# cytron.net
KiCad netlist of a schematic drawn in EAGLE
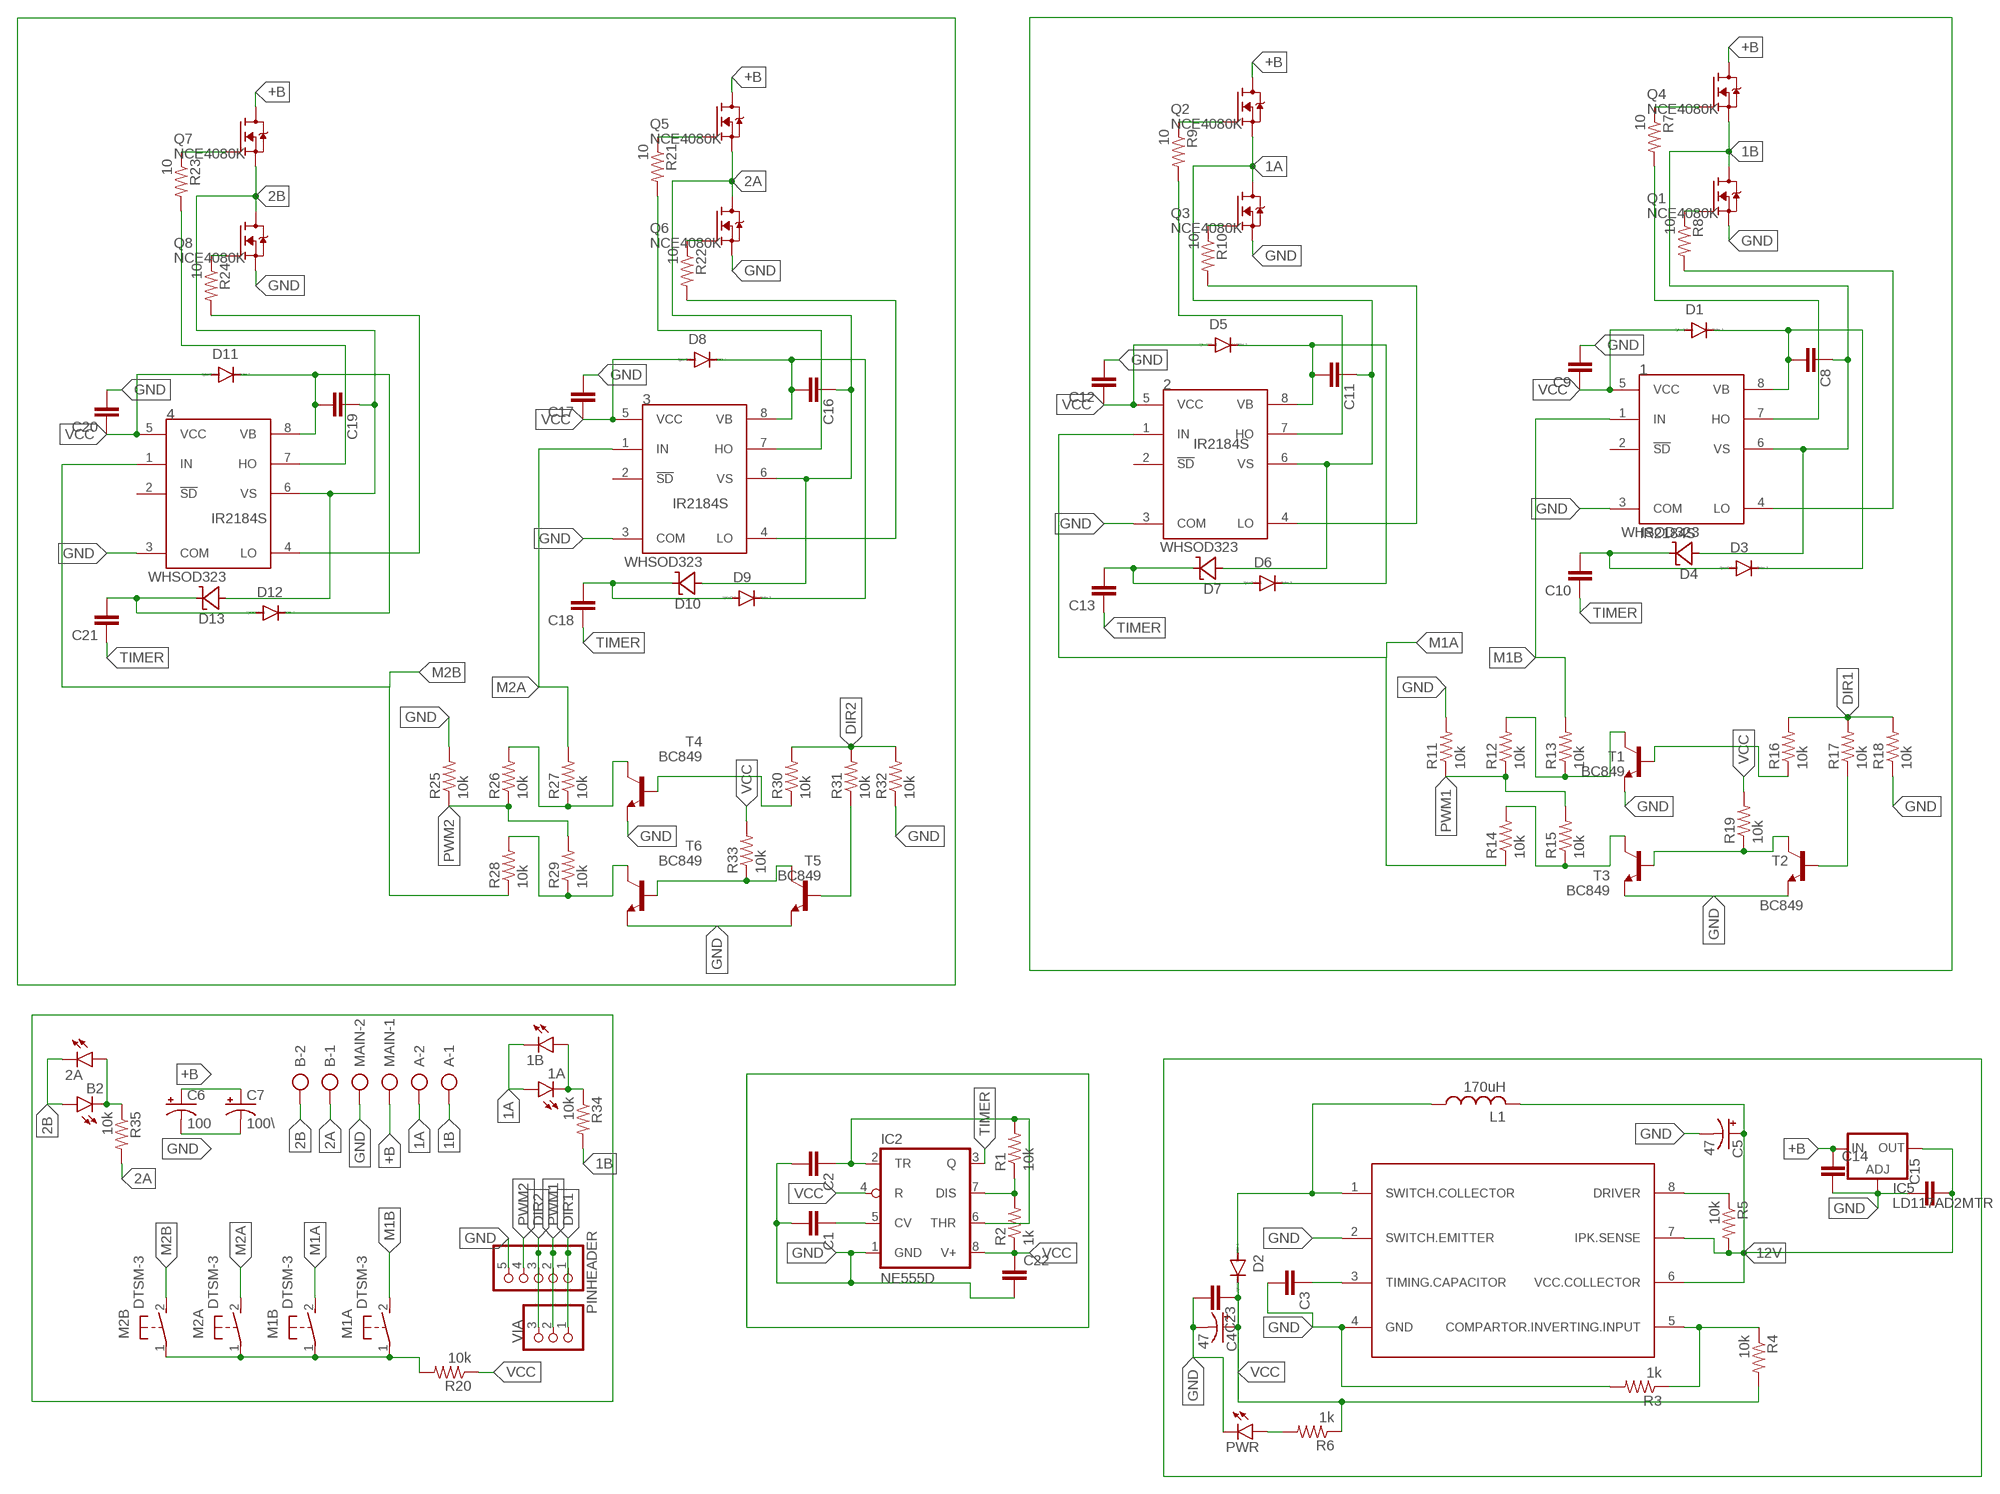
[diagram p0: schematic, sheet 1]

(export (version "E")
  (design (tool "Eeschema 10.0.6"))
  (components
    (comp (ref "1")
      (value "IR2184S")
      (footprint "eagle-import:SO08")
      (libsource (lib "eagle-import") (part "IR2184S"))
    )
    (comp (ref "1A")
      (value "LEDCHIPLED_1206")
      (footprint "eagle-import:CHIPLED_1206")
      (libsource (lib "eagle-import") (part "LEDCHIPLED_1206"))
    )
    (comp (ref "1B")
      (value "LEDCHIPLED_1206")
      (footprint "eagle-import:CHIPLED_1206")
      (libsource (lib "eagle-import") (part "LEDCHIPLED_1206"))
    )
    (comp (ref "2")
      (value "IR2184S")
      (footprint "eagle-import:SO08")
      (libsource (lib "eagle-import") (part "IR2184S"))
    )
    (comp (ref "2A")
      (value "LEDCHIPLED_1206")
      (footprint "eagle-import:CHIPLED_1206")
      (libsource (lib "eagle-import") (part "LEDCHIPLED_1206"))
    )
    (comp (ref "3")
      (value "IR2184S")
      (footprint "eagle-import:SO08")
      (libsource (lib "eagle-import") (part "IR2184S"))
    )
    (comp (ref "4")
      (value "IR2184S")
      (footprint "eagle-import:SO08")
      (libsource (lib "eagle-import") (part "IR2184S"))
    )
    (comp (ref "A")
      (value "AK300/22")
      (footprint "eagle-import:XTALRR488W60L1090T465H350B")
      (libsource (lib "eagle-import") (part "AK300/22"))
    )
    (comp (ref "B")
      (value "AK300/22")
      (footprint "eagle-import:XTALRR488W60L1090T465H350B")
      (libsource (lib "eagle-import") (part "AK300/22"))
    )
    (comp (ref "B2")
      (value "LEDCHIPLED_1206")
      (footprint "eagle-import:CHIPLED_1206")
      (libsource (lib "eagle-import") (part "LEDCHIPLED_1206"))
    )
    (comp (ref "C1")
      (value "C-EUC0805K")
      (footprint "eagle-import:C0805K")
      (libsource (lib "eagle-import") (part "C-EUC0805K"))
    )
    (comp (ref "C2")
      (value "C-EUC0805K")
      (footprint "eagle-import:C0805K")
      (libsource (lib "eagle-import") (part "C-EUC0805K"))
    )
    (comp (ref "C3")
      (value "C-EUC0805K")
      (footprint "eagle-import:C0805K")
      (libsource (lib "eagle-import") (part "C-EUC0805K"))
    )
    (comp (ref "C4")
      (value "47")
      (footprint "eagle-import:140CLH-1014")
      (libsource (lib "eagle-import") (part "CPOL-US140CLH-1014"))
    )
    (comp (ref "C5")
      (value "47")
      (footprint "eagle-import:140CLH-1014")
      (libsource (lib "eagle-import") (part "CPOL-US140CLH-1014"))
    )
    (comp (ref "C6")
      (value "100")
      (footprint "eagle-import:SANYO-OSCON_SMD_F12")
      (libsource (lib "eagle-import") (part "CPOL-USSANYO_SMD_F12"))
    )
    (comp (ref "C7")
      (value "100\\")
      (footprint "eagle-import:SANYO-OSCON_SMD_F12")
      (libsource (lib "eagle-import") (part "CPOL-USSANYO_SMD_F12"))
    )
    (comp (ref "C8")
      (value "C-EUC0805K")
      (footprint "eagle-import:C0805K")
      (libsource (lib "eagle-import") (part "C-EUC0805K"))
    )
    (comp (ref "C9")
      (value "C-EUC0805K")
      (footprint "eagle-import:C0805K")
      (libsource (lib "eagle-import") (part "C-EUC0805K"))
    )
    (comp (ref "C10")
      (value "C-EUC0805K")
      (footprint "eagle-import:C0805K")
      (libsource (lib "eagle-import") (part "C-EUC0805K"))
    )
    (comp (ref "C11")
      (value "C-EUC0805K")
      (footprint "eagle-import:C0805K")
      (libsource (lib "eagle-import") (part "C-EUC0805K"))
    )
    (comp (ref "C12")
      (value "C-EUC0805K")
      (footprint "eagle-import:C0805K")
      (libsource (lib "eagle-import") (part "C-EUC0805K"))
    )
    (comp (ref "C13")
      (value "C-EUC0805K")
      (footprint "eagle-import:C0805K")
      (libsource (lib "eagle-import") (part "C-EUC0805K"))
    )
    (comp (ref "C14")
      (value "C-EUC0805K")
      (footprint "eagle-import:C0805K")
      (libsource (lib "eagle-import") (part "C-EUC0805K"))
    )
    (comp (ref "C15")
      (value "C-EUC0805K")
      (footprint "eagle-import:C0805K")
      (libsource (lib "eagle-import") (part "C-EUC0805K"))
    )
    (comp (ref "C16")
      (value "C-EUC0805K")
      (footprint "eagle-import:C0805K")
      (libsource (lib "eagle-import") (part "C-EUC0805K"))
    )
    (comp (ref "C17")
      (value "C-EUC0805K")
      (footprint "eagle-import:C0805K")
      (libsource (lib "eagle-import") (part "C-EUC0805K"))
    )
    (comp (ref "C18")
      (value "C-EUC0805K")
      (footprint "eagle-import:C0805K")
      (libsource (lib "eagle-import") (part "C-EUC0805K"))
    )
    (comp (ref "C19")
      (value "C-EUC0805K")
      (footprint "eagle-import:C0805K")
      (libsource (lib "eagle-import") (part "C-EUC0805K"))
    )
    (comp (ref "C20")
      (value "C-EUC0805K")
      (footprint "eagle-import:C0805K")
      (libsource (lib "eagle-import") (part "C-EUC0805K"))
    )
    (comp (ref "C21")
      (value "C-EUC0805K")
      (footprint "eagle-import:C0805K")
      (libsource (lib "eagle-import") (part "C-EUC0805K"))
    )
    (comp (ref "C22")
      (value "C-EUC0805K")
      (footprint "eagle-import:C0805K")
      (libsource (lib "eagle-import") (part "C-EUC0805K"))
    )
    (comp (ref "C23")
      (value "C-EUC0805K")
      (footprint "eagle-import:C0805K")
      (libsource (lib "eagle-import") (part "C-EUC0805K"))
    )
    (comp (ref "D1")
      (value "DIODE-SMB")
      (footprint "eagle-import:SMB")
      (libsource (lib "eagle-import") (part "DIODE-SMB"))
    )
    (comp (ref "D2")
      (value "DIODE-SMB")
      (footprint "eagle-import:SMB")
      (libsource (lib "eagle-import") (part "DIODE-SMB"))
    )
    (comp (ref "D3")
      (value "DIODE-SMB")
      (footprint "eagle-import:SMB")
      (libsource (lib "eagle-import") (part "DIODE-SMB"))
    )
    (comp (ref "D4")
      (value "WHSOD323")
      (footprint "eagle-import:SOD323-W")
      (libsource (lib "eagle-import") (part "WHSOD323"))
    )
    (comp (ref "D5")
      (value "DIODE-SMB")
      (footprint "eagle-import:SMB")
      (libsource (lib "eagle-import") (part "DIODE-SMB"))
    )
    (comp (ref "D6")
      (value "DIODE-SMB")
      (footprint "eagle-import:SMB")
      (libsource (lib "eagle-import") (part "DIODE-SMB"))
    )
    (comp (ref "D7")
      (value "WHSOD323")
      (footprint "eagle-import:SOD323-W")
      (libsource (lib "eagle-import") (part "WHSOD323"))
    )
    (comp (ref "D8")
      (value "DIODE-SMB")
      (footprint "eagle-import:SMB")
      (libsource (lib "eagle-import") (part "DIODE-SMB"))
    )
    (comp (ref "D9")
      (value "DIODE-SMB")
      (footprint "eagle-import:SMB")
      (libsource (lib "eagle-import") (part "DIODE-SMB"))
    )
    (comp (ref "D10")
      (value "WHSOD323")
      (footprint "eagle-import:SOD323-W")
      (libsource (lib "eagle-import") (part "WHSOD323"))
    )
    (comp (ref "D11")
      (value "DIODE-SMB")
      (footprint "eagle-import:SMB")
      (libsource (lib "eagle-import") (part "DIODE-SMB"))
    )
    (comp (ref "D12")
      (value "DIODE-SMB")
      (footprint "eagle-import:SMB")
      (libsource (lib "eagle-import") (part "DIODE-SMB"))
    )
    (comp (ref "D13")
      (value "WHSOD323")
      (footprint "eagle-import:SOD323-W")
      (libsource (lib "eagle-import") (part "WHSOD323"))
    )
    (comp (ref "IC2")
      (value "NE555D")
      (footprint "eagle-import:SO08")
      (libsource (lib "eagle-import") (part "555DNE"))
    )
    (comp (ref "IC5")
      (value "LD117AD2MTR")
      (footprint "eagle-import:D2PACK")
      (libsource (lib "eagle-import") (part "LD117A?D2MTR"))
    )
    (comp (ref "L1")
      (value "170uH")
      (footprint "eagle-import:POWER-CHOKE_WE-TPC")
      (libsource (lib "eagle-import") (part "L-USWE-TPC"))
    )
    (comp (ref "M1A")
      (value "DTSM-3")
      (footprint "eagle-import:DTSM-3")
      (libsource (lib "eagle-import") (part "DTSM-3"))
    )
    (comp (ref "M1B")
      (value "DTSM-3")
      (footprint "eagle-import:DTSM-3")
      (libsource (lib "eagle-import") (part "DTSM-3"))
    )
    (comp (ref "M2A")
      (value "DTSM-3")
      (footprint "eagle-import:DTSM-3")
      (libsource (lib "eagle-import") (part "DTSM-3"))
    )
    (comp (ref "M2B")
      (value "DTSM-3")
      (footprint "eagle-import:DTSM-3")
      (libsource (lib "eagle-import") (part "DTSM-3"))
    )
    (comp (ref "MAIN")
      (value "AK300/22")
      (footprint "eagle-import:XTALRR488W60L1090T465H350B")
      (libsource (lib "eagle-import") (part "AK300/22"))
    )
    (comp (ref "PINHEADER")
      (value "PINHD-1X5")
      (footprint "eagle-import:1X05")
      (libsource (lib "eagle-import") (part "PINHD-1X5"))
    )
    (comp (ref "PWR")
      (value "LEDCHIPLED_1206")
      (footprint "eagle-import:CHIPLED_1206")
      (libsource (lib "eagle-import") (part "LEDCHIPLED_1206"))
    )
    (comp (ref "Q1")
      (value "NCE4080K")
      (footprint "eagle-import:TO252")
      (libsource (lib "eagle-import") (part "NCE4080K"))
    )
    (comp (ref "Q2")
      (value "NCE4080K")
      (footprint "eagle-import:TO252")
      (libsource (lib "eagle-import") (part "NCE4080K"))
    )
    (comp (ref "Q3")
      (value "NCE4080K")
      (footprint "eagle-import:TO252")
      (libsource (lib "eagle-import") (part "NCE4080K"))
    )
    (comp (ref "Q4")
      (value "NCE4080K")
      (footprint "eagle-import:TO252")
      (libsource (lib "eagle-import") (part "NCE4080K"))
    )
    (comp (ref "Q5")
      (value "NCE4080K")
      (footprint "eagle-import:TO252")
      (libsource (lib "eagle-import") (part "NCE4080K"))
    )
    (comp (ref "Q6")
      (value "NCE4080K")
      (footprint "eagle-import:TO252")
      (libsource (lib "eagle-import") (part "NCE4080K"))
    )
    (comp (ref "Q7")
      (value "NCE4080K")
      (footprint "eagle-import:TO252")
      (libsource (lib "eagle-import") (part "NCE4080K"))
    )
    (comp (ref "Q8")
      (value "NCE4080K")
      (footprint "eagle-import:TO252")
      (libsource (lib "eagle-import") (part "NCE4080K"))
    )
    (comp (ref "R1")
      (value "10k")
      (footprint "eagle-import:R1206")
      (libsource (lib "eagle-import") (part "R-US_R1206"))
    )
    (comp (ref "R2")
      (value "1k")
      (footprint "eagle-import:R1206")
      (libsource (lib "eagle-import") (part "R-US_R1206"))
    )
    (comp (ref "R3")
      (value "1k")
      (footprint "eagle-import:R1206")
      (libsource (lib "eagle-import") (part "R-US_R1206"))
    )
    (comp (ref "R4")
      (value "10k")
      (footprint "eagle-import:R1206")
      (libsource (lib "eagle-import") (part "R-US_R1206"))
    )
    (comp (ref "R5")
      (value "10k")
      (footprint "eagle-import:R1206")
      (libsource (lib "eagle-import") (part "R-US_R1206"))
    )
    (comp (ref "R6")
      (value "1k")
      (footprint "eagle-import:R1206")
      (libsource (lib "eagle-import") (part "R-US_R1206"))
    )
    (comp (ref "R7")
      (value "10")
      (footprint "eagle-import:R1206")
      (libsource (lib "eagle-import") (part "R-US_R1206"))
    )
    (comp (ref "R8")
      (value "10")
      (footprint "eagle-import:R1206")
      (libsource (lib "eagle-import") (part "R-US_R1206"))
    )
    (comp (ref "R9")
      (value "10")
      (footprint "eagle-import:R1206")
      (libsource (lib "eagle-import") (part "R-US_R1206"))
    )
    (comp (ref "R10")
      (value "10")
      (footprint "eagle-import:R1206")
      (libsource (lib "eagle-import") (part "R-US_R1206"))
    )
    (comp (ref "R11")
      (value "10k")
      (footprint "eagle-import:R1206")
      (libsource (lib "eagle-import") (part "R-US_R1206"))
    )
    (comp (ref "R12")
      (value "10k")
      (footprint "eagle-import:R1206")
      (libsource (lib "eagle-import") (part "R-US_R1206"))
    )
    (comp (ref "R13")
      (value "10k")
      (footprint "eagle-import:R1206")
      (libsource (lib "eagle-import") (part "R-US_R1206"))
    )
    (comp (ref "R14")
      (value "10k")
      (footprint "eagle-import:R1206")
      (libsource (lib "eagle-import") (part "R-US_R1206"))
    )
    (comp (ref "R15")
      (value "10k")
      (footprint "eagle-import:R1206")
      (libsource (lib "eagle-import") (part "R-US_R1206"))
    )
    (comp (ref "R16")
      (value "10k")
      (footprint "eagle-import:R1206")
      (libsource (lib "eagle-import") (part "R-US_R1206"))
    )
    (comp (ref "R17")
      (value "10k")
      (footprint "eagle-import:R1206")
      (libsource (lib "eagle-import") (part "R-US_R1206"))
    )
    (comp (ref "R18")
      (value "10k")
      (footprint "eagle-import:R1206")
      (libsource (lib "eagle-import") (part "R-US_R1206"))
    )
    (comp (ref "R19")
      (value "10k")
      (footprint "eagle-import:R1206")
      (libsource (lib "eagle-import") (part "R-US_R1206"))
    )
    (comp (ref "R20")
      (value "10k")
      (footprint "eagle-import:R1206")
      (libsource (lib "eagle-import") (part "R-US_R1206"))
    )
    (comp (ref "R21")
      (value "10")
      (footprint "eagle-import:R1206")
      (libsource (lib "eagle-import") (part "R-US_R1206"))
    )
    (comp (ref "R22")
      (value "10")
      (footprint "eagle-import:R1206")
      (libsource (lib "eagle-import") (part "R-US_R1206"))
    )
    (comp (ref "R23")
      (value "10")
      (footprint "eagle-import:R1206")
      (libsource (lib "eagle-import") (part "R-US_R1206"))
    )
    (comp (ref "R24")
      (value "10")
      (footprint "eagle-import:R1206")
      (libsource (lib "eagle-import") (part "R-US_R1206"))
    )
    (comp (ref "R25")
      (value "10k")
      (footprint "eagle-import:R1206")
      (libsource (lib "eagle-import") (part "R-US_R1206"))
    )
    (comp (ref "R26")
      (value "10k")
      (footprint "eagle-import:R1206")
      (libsource (lib "eagle-import") (part "R-US_R1206"))
    )
    (comp (ref "R27")
      (value "10k")
      (footprint "eagle-import:R1206")
      (libsource (lib "eagle-import") (part "R-US_R1206"))
    )
    (comp (ref "R28")
      (value "10k")
      (footprint "eagle-import:R1206")
      (libsource (lib "eagle-import") (part "R-US_R1206"))
    )
    (comp (ref "R29")
      (value "10k")
      (footprint "eagle-import:R1206")
      (libsource (lib "eagle-import") (part "R-US_R1206"))
    )
    (comp (ref "R30")
      (value "10k")
      (footprint "eagle-import:R1206")
      (libsource (lib "eagle-import") (part "R-US_R1206"))
    )
    (comp (ref "R31")
      (value "10k")
      (footprint "eagle-import:R1206")
      (libsource (lib "eagle-import") (part "R-US_R1206"))
    )
    (comp (ref "R32")
      (value "10k")
      (footprint "eagle-import:R1206")
      (libsource (lib "eagle-import") (part "R-US_R1206"))
    )
    (comp (ref "R33")
      (value "10k")
      (footprint "eagle-import:R1206")
      (libsource (lib "eagle-import") (part "R-US_R1206"))
    )
    (comp (ref "R34")
      (value "10k")
      (footprint "eagle-import:R1206")
      (libsource (lib "eagle-import") (part "R-US_R1206"))
    )
    (comp (ref "R35")
      (value "10k")
      (footprint "eagle-import:R1206")
      (libsource (lib "eagle-import") (part "R-US_R1206"))
    )
    (comp (ref "T1")
      (value "BC849")
      (footprint "eagle-import:SOT23")
      (libsource (lib "eagle-import") (part "BC849"))
    )
    (comp (ref "T2")
      (value "BC849")
      (footprint "eagle-import:SOT23")
      (libsource (lib "eagle-import") (part "BC849"))
    )
    (comp (ref "T3")
      (value "BC849")
      (footprint "eagle-import:SOT23")
      (libsource (lib "eagle-import") (part "BC849"))
    )
    (comp (ref "T4")
      (value "BC849")
      (footprint "eagle-import:SOT23")
      (libsource (lib "eagle-import") (part "BC849"))
    )
    (comp (ref "T5")
      (value "BC849")
      (footprint "eagle-import:SOT23")
      (libsource (lib "eagle-import") (part "BC849"))
    )
    (comp (ref "T6")
      (value "BC849")
      (footprint "eagle-import:SOT23")
      (libsource (lib "eagle-import") (part "BC849"))
    )
    (comp (ref "U$1")
      (value "AB34063")
      (footprint "eagle-import:SO8")
      (libsource (lib "eagle-import") (part "AB34063"))
    )
    (comp (ref "VIA")
      (value "PINHD-1X3")
      (footprint "eagle-import:1X03")
      (libsource (lib "eagle-import") (part "PINHD-1X3"))
    )
  )
  (nets
    (net (code "1") (name "+B") (class "Default")
      (node (ref "C14") (pin "1") (pinfunction "1_1") (pintype "passive"))
      (node (ref "C6") (pin "+") (pinfunction "+_+") (pintype "passive"))
      (node (ref "C7") (pin "+") (pinfunction "+_+") (pintype "passive"))
      (node (ref "IC5") (pin "1") (pinfunction "IN_1") (pintype "input"))
      (node (ref "MAIN") (pin "1") (pinfunction "KL_1") (pintype "passive"))
      (node (ref "Q2") (pin "3") (pinfunction "D_3") (pintype "passive"))
      (node (ref "Q4") (pin "3") (pinfunction "D_3") (pintype "passive"))
      (node (ref "Q5") (pin "3") (pinfunction "D_3") (pintype "passive"))
      (node (ref "Q7") (pin "3") (pinfunction "D_3") (pintype "passive"))
    )
    (net (code "2") (name "1A") (class "Default")
      (node (ref "1A") (pin "A") (pinfunction "A_A") (pintype "passive"))
      (node (ref "1B") (pin "C") (pinfunction "C_C") (pintype "passive"))
      (node (ref "2") (pin "6") (pinfunction "VS_6") (pintype "power_in"))
      (node (ref "A") (pin "2") (pinfunction "KL_2") (pintype "passive"))
      (node (ref "C11") (pin "1") (pinfunction "1_1") (pintype "passive"))
      (node (ref "D7") (pin "A") (pinfunction "A_A") (pintype "passive"))
      (node (ref "Q2") (pin "2") (pinfunction "S_2") (pintype "passive"))
      (node (ref "Q3") (pin "3") (pinfunction "D_3") (pintype "passive"))
    )
    (net (code "3") (name "1B") (class "Default")
      (node (ref "1") (pin "6") (pinfunction "VS_6") (pintype "power_in"))
      (node (ref "A") (pin "1") (pinfunction "KL_1") (pintype "passive"))
      (node (ref "C8") (pin "1") (pinfunction "1_1") (pintype "passive"))
      (node (ref "D4") (pin "A") (pinfunction "A_A") (pintype "passive"))
      (node (ref "Q1") (pin "3") (pinfunction "D_3") (pintype "passive"))
      (node (ref "Q4") (pin "2") (pinfunction "S_2") (pintype "passive"))
      (node (ref "R34") (pin "2") (pinfunction "2_2") (pintype "passive"))
    )
    (net (code "4") (name "2A") (class "Default")
      (node (ref "3") (pin "6") (pinfunction "VS_6") (pintype "power_in"))
      (node (ref "B") (pin "1") (pinfunction "KL_1") (pintype "passive"))
      (node (ref "C16") (pin "1") (pinfunction "1_1") (pintype "passive"))
      (node (ref "D10") (pin "A") (pinfunction "A_A") (pintype "passive"))
      (node (ref "Q5") (pin "2") (pinfunction "S_2") (pintype "passive"))
      (node (ref "Q6") (pin "3") (pinfunction "D_3") (pintype "passive"))
      (node (ref "R35") (pin "2") (pinfunction "2_2") (pintype "passive"))
    )
    (net (code "5") (name "2B") (class "Default")
      (node (ref "2A") (pin "C") (pinfunction "C_C") (pintype "passive"))
      (node (ref "4") (pin "6") (pinfunction "VS_6") (pintype "power_in"))
      (node (ref "B") (pin "2") (pinfunction "KL_2") (pintype "passive"))
      (node (ref "B2") (pin "A") (pinfunction "A_A") (pintype "passive"))
      (node (ref "C19") (pin "1") (pinfunction "1_1") (pintype "passive"))
      (node (ref "D13") (pin "A") (pinfunction "A_A") (pintype "passive"))
      (node (ref "Q7") (pin "2") (pinfunction "S_2") (pintype "passive"))
      (node (ref "Q8") (pin "3") (pinfunction "D_3") (pintype "passive"))
    )
    (net (code "6") (name "12V") (class "Default")
      (node (ref "C15") (pin "2") (pinfunction "2_2") (pintype "passive"))
      (node (ref "C5") (pin "+") (pinfunction "+_+") (pintype "passive"))
      (node (ref "IC5") (pin "3") (pinfunction "OUT_3") (pintype "passive"))
      (node (ref "L1") (pin "2") (pinfunction "2_2") (pintype "passive"))
      (node (ref "R5") (pin "2") (pinfunction "2_2") (pintype "passive"))
      (node (ref "U$1") (pin "6") (pinfunction "VCC.COLLECTOR_6") (pintype "bidirectional"))
      (node (ref "U$1") (pin "7") (pinfunction "IPK.SENSE_7") (pintype "bidirectional"))
    )
    (net (code "7") (name "DIR1") (class "Default")
      (node (ref "PINHEADER") (pin "1") (pinfunction "1_1") (pintype "passive"))
      (node (ref "R16") (pin "2") (pinfunction "2_2") (pintype "passive"))
      (node (ref "R17") (pin "2") (pinfunction "2_2") (pintype "passive"))
      (node (ref "R18") (pin "2") (pinfunction "2_2") (pintype "passive"))
      (node (ref "VIA") (pin "1") (pinfunction "1_1") (pintype "passive"))
    )
    (net (code "8") (name "DIR2") (class "Default")
      (node (ref "PINHEADER") (pin "3") (pinfunction "3_3") (pintype "passive"))
      (node (ref "R30") (pin "2") (pinfunction "2_2") (pintype "passive"))
      (node (ref "R31") (pin "2") (pinfunction "2_2") (pintype "passive"))
      (node (ref "R32") (pin "2") (pinfunction "2_2") (pintype "passive"))
      (node (ref "VIA") (pin "3") (pinfunction "3_3") (pintype "passive"))
    )
    (net (code "9") (name "GND") (class "Default")
      (node (ref "1") (pin "3") (pinfunction "COM_3") (pintype "power_in"))
      (node (ref "2") (pin "3") (pinfunction "COM_3") (pintype "power_in"))
      (node (ref "3") (pin "3") (pinfunction "COM_3") (pintype "power_in"))
      (node (ref "4") (pin "3") (pinfunction "COM_3") (pintype "power_in"))
      (node (ref "C1") (pin "2") (pinfunction "2_2") (pintype "passive"))
      (node (ref "C12") (pin "2") (pinfunction "2_2") (pintype "passive"))
      (node (ref "C14") (pin "2") (pinfunction "2_2") (pintype "passive"))
      (node (ref "C15") (pin "1") (pinfunction "1_1") (pintype "passive"))
      (node (ref "C17") (pin "2") (pinfunction "2_2") (pintype "passive"))
      (node (ref "C2") (pin "2") (pinfunction "2_2") (pintype "passive"))
      (node (ref "C20") (pin "2") (pinfunction "2_2") (pintype "passive"))
      (node (ref "C22") (pin "2") (pinfunction "2_2") (pintype "passive"))
      (node (ref "C23") (pin "2") (pinfunction "2_2") (pintype "passive"))
      (node (ref "C3") (pin "2") (pinfunction "2_2") (pintype "passive"))
      (node (ref "C4") (pin "-") (pinfunction "-_-") (pintype "passive"))
      (node (ref "C5") (pin "-") (pinfunction "-_-") (pintype "passive"))
      (node (ref "C6") (pin "-") (pinfunction "-_-") (pintype "passive"))
      (node (ref "C7") (pin "-") (pinfunction "-_-") (pintype "passive"))
      (node (ref "C9") (pin "2") (pinfunction "2_2") (pintype "passive"))
      (node (ref "IC2") (pin "1") (pinfunction "GND_1") (pintype "power_in"))
      (node (ref "IC5") (pin "2") (pinfunction "ADJ_2") (pintype "input"))
      (node (ref "MAIN") (pin "2") (pinfunction "KL_2") (pintype "passive"))
      (node (ref "PINHEADER") (pin "5") (pinfunction "5_5") (pintype "passive"))
      (node (ref "PWR") (pin "C") (pinfunction "C_C") (pintype "passive"))
      (node (ref "Q1") (pin "2") (pinfunction "S_2") (pintype "passive"))
      (node (ref "Q3") (pin "2") (pinfunction "S_2") (pintype "passive"))
      (node (ref "Q6") (pin "2") (pinfunction "S_2") (pintype "passive"))
      (node (ref "Q8") (pin "2") (pinfunction "S_2") (pintype "passive"))
      (node (ref "R11") (pin "2") (pinfunction "2_2") (pintype "passive"))
      (node (ref "R18") (pin "1") (pinfunction "1_1") (pintype "passive"))
      (node (ref "R25") (pin "2") (pinfunction "2_2") (pintype "passive"))
      (node (ref "R3") (pin "2") (pinfunction "2_2") (pintype "passive"))
      (node (ref "R32") (pin "1") (pinfunction "1_1") (pintype "passive"))
      (node (ref "T1") (pin "2") (pinfunction "E_2") (pintype "passive"))
      (node (ref "T2") (pin "2") (pinfunction "E_2") (pintype "passive"))
      (node (ref "T3") (pin "2") (pinfunction "E_2") (pintype "passive"))
      (node (ref "T4") (pin "2") (pinfunction "E_2") (pintype "passive"))
      (node (ref "T5") (pin "2") (pinfunction "E_2") (pintype "passive"))
      (node (ref "T6") (pin "2") (pinfunction "E_2") (pintype "passive"))
      (node (ref "U$1") (pin "2") (pinfunction "SWITCH.EMITTER_2") (pintype "bidirectional"))
      (node (ref "U$1") (pin "4") (pinfunction "GND_4") (pintype "bidirectional"))
    )
    (net (code "10") (name "M1A") (class "Default")
      (node (ref "2") (pin "1") (pinfunction "IN_1") (pintype "input"))
      (node (ref "M1B") (pin "2") (pinfunction "2_2") (pintype "passive"))
      (node (ref "R14") (pin "1") (pinfunction "1_1") (pintype "passive"))
    )
    (net (code "11") (name "M1B") (class "Default")
      (node (ref "1") (pin "1") (pinfunction "IN_1") (pintype "input"))
      (node (ref "M1A") (pin "2") (pinfunction "2_2") (pintype "passive"))
      (node (ref "R13") (pin "2") (pinfunction "2_2") (pintype "passive"))
    )
    (net (code "12") (name "M2A") (class "Default")
      (node (ref "3") (pin "1") (pinfunction "IN_1") (pintype "input"))
      (node (ref "M2A") (pin "2") (pinfunction "2_2") (pintype "passive"))
      (node (ref "R27") (pin "2") (pinfunction "2_2") (pintype "passive"))
    )
    (net (code "13") (name "M2B") (class "Default")
      (node (ref "4") (pin "1") (pinfunction "IN_1") (pintype "input"))
      (node (ref "M2B") (pin "2") (pinfunction "2_2") (pintype "passive"))
      (node (ref "R28") (pin "1") (pinfunction "1_1") (pintype "passive"))
    )
    (net (code "14") (name "Net-(1-HO)") (class "Default")
      (node (ref "1") (pin "7") (pinfunction "HO_7") (pintype "output"))
      (node (ref "R7") (pin "2") (pinfunction "2_2") (pintype "passive"))
    )
    (net (code "15") (name "Net-(1-LO)") (class "Default")
      (node (ref "1") (pin "4") (pinfunction "LO_4") (pintype "output"))
      (node (ref "R8") (pin "2") (pinfunction "2_2") (pintype "passive"))
    )
    (net (code "16") (name "Net-(1-VB)") (class "Default")
      (node (ref "1") (pin "8") (pinfunction "VB_8") (pintype "power_in"))
      (node (ref "C8") (pin "2") (pinfunction "2_2") (pintype "passive"))
      (node (ref "D1") (pin "C") (pinfunction "C_C") (pintype "passive"))
      (node (ref "D3") (pin "C") (pinfunction "C_C") (pintype "passive"))
    )
    (net (code "17") (name "Net-(1A-PadC)") (class "Default")
      (node (ref "1A") (pin "C") (pinfunction "C_C") (pintype "passive"))
      (node (ref "1B") (pin "A") (pinfunction "A_A") (pintype "passive"))
      (node (ref "R34") (pin "1") (pinfunction "1_1") (pintype "passive"))
    )
    (net (code "18") (name "Net-(2-HO)") (class "Default")
      (node (ref "2") (pin "7") (pinfunction "HO_7") (pintype "output"))
      (node (ref "R9") (pin "2") (pinfunction "2_2") (pintype "passive"))
    )
    (net (code "19") (name "Net-(2-LO)") (class "Default")
      (node (ref "2") (pin "4") (pinfunction "LO_4") (pintype "output"))
      (node (ref "R10") (pin "2") (pinfunction "2_2") (pintype "passive"))
    )
    (net (code "20") (name "Net-(2-VB)") (class "Default")
      (node (ref "2") (pin "8") (pinfunction "VB_8") (pintype "power_in"))
      (node (ref "C11") (pin "2") (pinfunction "2_2") (pintype "passive"))
      (node (ref "D5") (pin "C") (pinfunction "C_C") (pintype "passive"))
      (node (ref "D6") (pin "C") (pinfunction "C_C") (pintype "passive"))
    )
    (net (code "21") (name "Net-(2A-PadA)") (class "Default")
      (node (ref "2A") (pin "A") (pinfunction "A_A") (pintype "passive"))
      (node (ref "B2") (pin "C") (pinfunction "C_C") (pintype "passive"))
      (node (ref "R35") (pin "1") (pinfunction "1_1") (pintype "passive"))
    )
    (net (code "22") (name "Net-(3-HO)") (class "Default")
      (node (ref "3") (pin "7") (pinfunction "HO_7") (pintype "output"))
      (node (ref "R21") (pin "2") (pinfunction "2_2") (pintype "passive"))
    )
    (net (code "23") (name "Net-(3-LO)") (class "Default")
      (node (ref "3") (pin "4") (pinfunction "LO_4") (pintype "output"))
      (node (ref "R22") (pin "2") (pinfunction "2_2") (pintype "passive"))
    )
    (net (code "24") (name "Net-(3-VB)") (class "Default")
      (node (ref "3") (pin "8") (pinfunction "VB_8") (pintype "power_in"))
      (node (ref "C16") (pin "2") (pinfunction "2_2") (pintype "passive"))
      (node (ref "D8") (pin "C") (pinfunction "C_C") (pintype "passive"))
      (node (ref "D9") (pin "C") (pinfunction "C_C") (pintype "passive"))
    )
    (net (code "25") (name "Net-(4-HO)") (class "Default")
      (node (ref "4") (pin "7") (pinfunction "HO_7") (pintype "output"))
      (node (ref "R23") (pin "2") (pinfunction "2_2") (pintype "passive"))
    )
    (net (code "26") (name "Net-(4-LO)") (class "Default")
      (node (ref "4") (pin "4") (pinfunction "LO_4") (pintype "output"))
      (node (ref "R24") (pin "2") (pinfunction "2_2") (pintype "passive"))
    )
    (net (code "27") (name "Net-(4-VB)") (class "Default")
      (node (ref "4") (pin "8") (pinfunction "VB_8") (pintype "power_in"))
      (node (ref "C19") (pin "2") (pinfunction "2_2") (pintype "passive"))
      (node (ref "D11") (pin "C") (pinfunction "C_C") (pintype "passive"))
      (node (ref "D12") (pin "C") (pinfunction "C_C") (pintype "passive"))
    )
    (net (code "28") (name "Net-(C10-Pad2)") (class "Default")
      (node (ref "C10") (pin "2") (pinfunction "2_2") (pintype "passive"))
      (node (ref "D3") (pin "A") (pinfunction "A_A") (pintype "passive"))
      (node (ref "D4") (pin "C") (pinfunction "C_C") (pintype "passive"))
    )
    (net (code "29") (name "Net-(C13-Pad2)") (class "Default")
      (node (ref "C13") (pin "2") (pinfunction "2_2") (pintype "passive"))
      (node (ref "D6") (pin "A") (pinfunction "A_A") (pintype "passive"))
      (node (ref "D7") (pin "C") (pinfunction "C_C") (pintype "passive"))
    )
    (net (code "30") (name "Net-(C18-Pad2)") (class "Default")
      (node (ref "C18") (pin "2") (pinfunction "2_2") (pintype "passive"))
      (node (ref "D10") (pin "C") (pinfunction "C_C") (pintype "passive"))
      (node (ref "D9") (pin "A") (pinfunction "A_A") (pintype "passive"))
    )
    (net (code "31") (name "Net-(C21-Pad2)") (class "Default")
      (node (ref "C21") (pin "2") (pinfunction "2_2") (pintype "passive"))
      (node (ref "D12") (pin "A") (pinfunction "A_A") (pintype "passive"))
      (node (ref "D13") (pin "C") (pinfunction "C_C") (pintype "passive"))
    )
    (net (code "32") (name "Net-(IC2-CV)") (class "Default")
      (node (ref "C1") (pin "1") (pinfunction "1_1") (pintype "passive"))
      (node (ref "IC2") (pin "5") (pinfunction "CV_5") (pintype "input"))
    )
    (net (code "33") (name "Net-(IC2-DIS)") (class "Default")
      (node (ref "IC2") (pin "7") (pinfunction "DIS_7") (pintype "input"))
      (node (ref "R1") (pin "1") (pinfunction "1_1") (pintype "passive"))
      (node (ref "R2") (pin "2") (pinfunction "2_2") (pintype "passive"))
    )
    (net (code "34") (name "Net-(IC2-THR)") (class "Default")
      (node (ref "C2") (pin "1") (pinfunction "1_1") (pintype "passive"))
      (node (ref "IC2") (pin "2") (pinfunction "TR_2") (pintype "input"))
      (node (ref "IC2") (pin "6") (pinfunction "THR_6") (pintype "input"))
      (node (ref "R1") (pin "2") (pinfunction "2_2") (pintype "passive"))
    )
    (net (code "35") (name "Net-(M1A-Pad1)") (class "Default")
      (node (ref "M1A") (pin "1") (pinfunction "1_1") (pintype "passive"))
      (node (ref "M1B") (pin "1") (pinfunction "1_1") (pintype "passive"))
      (node (ref "M2A") (pin "1") (pinfunction "1_1") (pintype "passive"))
      (node (ref "M2B") (pin "1") (pinfunction "1_1") (pintype "passive"))
      (node (ref "R20") (pin "2") (pinfunction "2_2") (pintype "passive"))
    )
    (net (code "36") (name "Net-(PWR-PadA)") (class "Default")
      (node (ref "PWR") (pin "A") (pinfunction "A_A") (pintype "passive"))
      (node (ref "R6") (pin "2") (pinfunction "2_2") (pintype "passive"))
    )
    (net (code "37") (name "Net-(Q1-G)") (class "Default")
      (node (ref "Q1") (pin "1") (pinfunction "G_1") (pintype "passive"))
      (node (ref "R8") (pin "1") (pinfunction "1_1") (pintype "passive"))
    )
    (net (code "38") (name "Net-(Q2-G)") (class "Default")
      (node (ref "Q2") (pin "1") (pinfunction "G_1") (pintype "passive"))
      (node (ref "R9") (pin "1") (pinfunction "1_1") (pintype "passive"))
    )
    (net (code "39") (name "Net-(Q3-G)") (class "Default")
      (node (ref "Q3") (pin "1") (pinfunction "G_1") (pintype "passive"))
      (node (ref "R10") (pin "1") (pinfunction "1_1") (pintype "passive"))
    )
    (net (code "40") (name "Net-(Q4-G)") (class "Default")
      (node (ref "Q4") (pin "1") (pinfunction "G_1") (pintype "passive"))
      (node (ref "R7") (pin "1") (pinfunction "1_1") (pintype "passive"))
    )
    (net (code "41") (name "Net-(Q5-G)") (class "Default")
      (node (ref "Q5") (pin "1") (pinfunction "G_1") (pintype "passive"))
      (node (ref "R21") (pin "1") (pinfunction "1_1") (pintype "passive"))
    )
    (net (code "42") (name "Net-(Q6-G)") (class "Default")
      (node (ref "Q6") (pin "1") (pinfunction "G_1") (pintype "passive"))
      (node (ref "R22") (pin "1") (pinfunction "1_1") (pintype "passive"))
    )
    (net (code "43") (name "Net-(Q7-G)") (class "Default")
      (node (ref "Q7") (pin "1") (pinfunction "G_1") (pintype "passive"))
      (node (ref "R23") (pin "1") (pinfunction "1_1") (pintype "passive"))
    )
    (net (code "44") (name "Net-(Q8-G)") (class "Default")
      (node (ref "Q8") (pin "1") (pinfunction "G_1") (pintype "passive"))
      (node (ref "R24") (pin "1") (pinfunction "1_1") (pintype "passive"))
    )
    (net (code "45") (name "Net-(T1-B)") (class "Default")
      (node (ref "R16") (pin "1") (pinfunction "1_1") (pintype "passive"))
      (node (ref "T1") (pin "1") (pinfunction "B_1") (pintype "passive"))
    )
    (net (code "46") (name "Net-(T1-C)") (class "Default")
      (node (ref "R12") (pin "2") (pinfunction "2_2") (pintype "passive"))
      (node (ref "R13") (pin "1") (pinfunction "1_1") (pintype "passive"))
      (node (ref "T1") (pin "3") (pinfunction "C_3") (pintype "passive"))
    )
    (net (code "47") (name "Net-(T2-B)") (class "Default")
      (node (ref "R17") (pin "1") (pinfunction "1_1") (pintype "passive"))
      (node (ref "T2") (pin "1") (pinfunction "B_1") (pintype "passive"))
    )
    (net (code "48") (name "Net-(T2-C)") (class "Default")
      (node (ref "R19") (pin "1") (pinfunction "1_1") (pintype "passive"))
      (node (ref "T2") (pin "3") (pinfunction "C_3") (pintype "passive"))
      (node (ref "T3") (pin "1") (pinfunction "B_1") (pintype "passive"))
    )
    (net (code "49") (name "Net-(T3-C)") (class "Default")
      (node (ref "R14") (pin "2") (pinfunction "2_2") (pintype "passive"))
      (node (ref "R15") (pin "1") (pinfunction "1_1") (pintype "passive"))
      (node (ref "T3") (pin "3") (pinfunction "C_3") (pintype "passive"))
    )
    (net (code "50") (name "Net-(T4-B)") (class "Default")
      (node (ref "R30") (pin "1") (pinfunction "1_1") (pintype "passive"))
      (node (ref "T4") (pin "1") (pinfunction "B_1") (pintype "passive"))
    )
    (net (code "51") (name "Net-(T4-C)") (class "Default")
      (node (ref "R26") (pin "2") (pinfunction "2_2") (pintype "passive"))
      (node (ref "R27") (pin "1") (pinfunction "1_1") (pintype "passive"))
      (node (ref "T4") (pin "3") (pinfunction "C_3") (pintype "passive"))
    )
    (net (code "52") (name "Net-(T5-B)") (class "Default")
      (node (ref "R31") (pin "1") (pinfunction "1_1") (pintype "passive"))
      (node (ref "T5") (pin "1") (pinfunction "B_1") (pintype "passive"))
    )
    (net (code "53") (name "Net-(T5-C)") (class "Default")
      (node (ref "R33") (pin "1") (pinfunction "1_1") (pintype "passive"))
      (node (ref "T5") (pin "3") (pinfunction "C_3") (pintype "passive"))
      (node (ref "T6") (pin "1") (pinfunction "B_1") (pintype "passive"))
    )
    (net (code "54") (name "Net-(T6-C)") (class "Default")
      (node (ref "R28") (pin "2") (pinfunction "2_2") (pintype "passive"))
      (node (ref "R29") (pin "1") (pinfunction "1_1") (pintype "passive"))
      (node (ref "T6") (pin "3") (pinfunction "C_3") (pintype "passive"))
    )
    (net (code "55") (name "Net-(U$1-COMPARTOR.INVERTING.INPUT)") (class "Default")
      (node (ref "R3") (pin "1") (pinfunction "1_1") (pintype "passive"))
      (node (ref "R4") (pin "1") (pinfunction "1_1") (pintype "passive"))
      (node (ref "U$1") (pin "5") (pinfunction "COMPARTOR.INVERTING.INPUT_5") (pintype "bidirectional"))
    )
    (net (code "56") (name "Net-(U$1-DRIVER)") (class "Default")
      (node (ref "R5") (pin "1") (pinfunction "1_1") (pintype "passive"))
      (node (ref "U$1") (pin "8") (pinfunction "DRIVER_8") (pintype "bidirectional"))
    )
    (net (code "57") (name "Net-(U$1-SWITCH.COLLECTOR)") (class "Default")
      (node (ref "D2") (pin "A") (pinfunction "A_A") (pintype "passive"))
      (node (ref "L1") (pin "1") (pinfunction "1_1") (pintype "passive"))
      (node (ref "U$1") (pin "1") (pinfunction "SWITCH.COLLECTOR_1") (pintype "bidirectional"))
    )
    (net (code "58") (name "Net-(U$1-TIMING.CAPACITOR)") (class "Default")
      (node (ref "C3") (pin "1") (pinfunction "1_1") (pintype "passive"))
      (node (ref "U$1") (pin "3") (pinfunction "TIMING.CAPACITOR_3") (pintype "bidirectional"))
    )
    (net (code "59") (name "PWM1") (class "Default")
      (node (ref "PINHEADER") (pin "2") (pinfunction "2_2") (pintype "passive"))
      (node (ref "R11") (pin "1") (pinfunction "1_1") (pintype "passive"))
      (node (ref "R12") (pin "1") (pinfunction "1_1") (pintype "passive"))
      (node (ref "R15") (pin "2") (pinfunction "2_2") (pintype "passive"))
      (node (ref "VIA") (pin "2") (pinfunction "2_2") (pintype "passive"))
    )
    (net (code "60") (name "PWM2") (class "Default")
      (node (ref "PINHEADER") (pin "4") (pinfunction "4_4") (pintype "passive"))
      (node (ref "R25") (pin "1") (pinfunction "1_1") (pintype "passive"))
      (node (ref "R26") (pin "1") (pinfunction "1_1") (pintype "passive"))
      (node (ref "R29") (pin "2") (pinfunction "2_2") (pintype "passive"))
    )
    (net (code "61") (name "TIMER") (class "Default")
      (node (ref "C10") (pin "1") (pinfunction "1_1") (pintype "passive"))
      (node (ref "C13") (pin "1") (pinfunction "1_1") (pintype "passive"))
      (node (ref "C18") (pin "1") (pinfunction "1_1") (pintype "passive"))
      (node (ref "C21") (pin "1") (pinfunction "1_1") (pintype "passive"))
      (node (ref "IC2") (pin "3") (pinfunction "Q_3") (pintype "output"))
    )
    (net (code "62") (name "VCC") (class "Default")
      (node (ref "1") (pin "5") (pinfunction "VCC_5") (pintype "power_in"))
      (node (ref "2") (pin "5") (pinfunction "VCC_5") (pintype "power_in"))
      (node (ref "3") (pin "5") (pinfunction "VCC_5") (pintype "power_in"))
      (node (ref "4") (pin "5") (pinfunction "VCC_5") (pintype "power_in"))
      (node (ref "C12") (pin "1") (pinfunction "1_1") (pintype "passive"))
      (node (ref "C17") (pin "1") (pinfunction "1_1") (pintype "passive"))
      (node (ref "C20") (pin "1") (pinfunction "1_1") (pintype "passive"))
      (node (ref "C22") (pin "1") (pinfunction "1_1") (pintype "passive"))
      (node (ref "C23") (pin "1") (pinfunction "1_1") (pintype "passive"))
      (node (ref "C4") (pin "+") (pinfunction "+_+") (pintype "passive"))
      (node (ref "C9") (pin "1") (pinfunction "1_1") (pintype "passive"))
      (node (ref "D1") (pin "A") (pinfunction "A_A") (pintype "passive"))
      (node (ref "D11") (pin "A") (pinfunction "A_A") (pintype "passive"))
      (node (ref "D2") (pin "C") (pinfunction "C_C") (pintype "passive"))
      (node (ref "D5") (pin "A") (pinfunction "A_A") (pintype "passive"))
      (node (ref "D8") (pin "A") (pinfunction "A_A") (pintype "passive"))
      (node (ref "IC2") (pin "4") (pinfunction "R_4") (pintype "input"))
      (node (ref "IC2") (pin "8") (pinfunction "V+_8") (pintype "power_in"))
      (node (ref "R19") (pin "2") (pinfunction "2_2") (pintype "passive"))
      (node (ref "R2") (pin "1") (pinfunction "1_1") (pintype "passive"))
      (node (ref "R20") (pin "1") (pinfunction "1_1") (pintype "passive"))
      (node (ref "R33") (pin "2") (pinfunction "2_2") (pintype "passive"))
      (node (ref "R4") (pin "2") (pinfunction "2_2") (pintype "passive"))
      (node (ref "R6") (pin "1") (pinfunction "1_1") (pintype "passive"))
    )
    (net (code "63") (name "unconnected-(1-~{SD}-Pad2)") (class "Default")
      (node (ref "1") (pin "2") (pinfunction "~{SD}_2") (pintype "input"))
    )
    (net (code "64") (name "unconnected-(2-~{SD}-Pad2)") (class "Default")
      (node (ref "2") (pin "2") (pinfunction "~{SD}_2") (pintype "input"))
    )
    (net (code "65") (name "unconnected-(3-~{SD}-Pad2)") (class "Default")
      (node (ref "3") (pin "2") (pinfunction "~{SD}_2") (pintype "input"))
    )
    (net (code "66") (name "unconnected-(4-~{SD}-Pad2)") (class "Default")
      (node (ref "4") (pin "2") (pinfunction "~{SD}_2") (pintype "input"))
    )
  )
)
